# robotek2.net
KiCad netlist of a schematic drawn in EAGLE
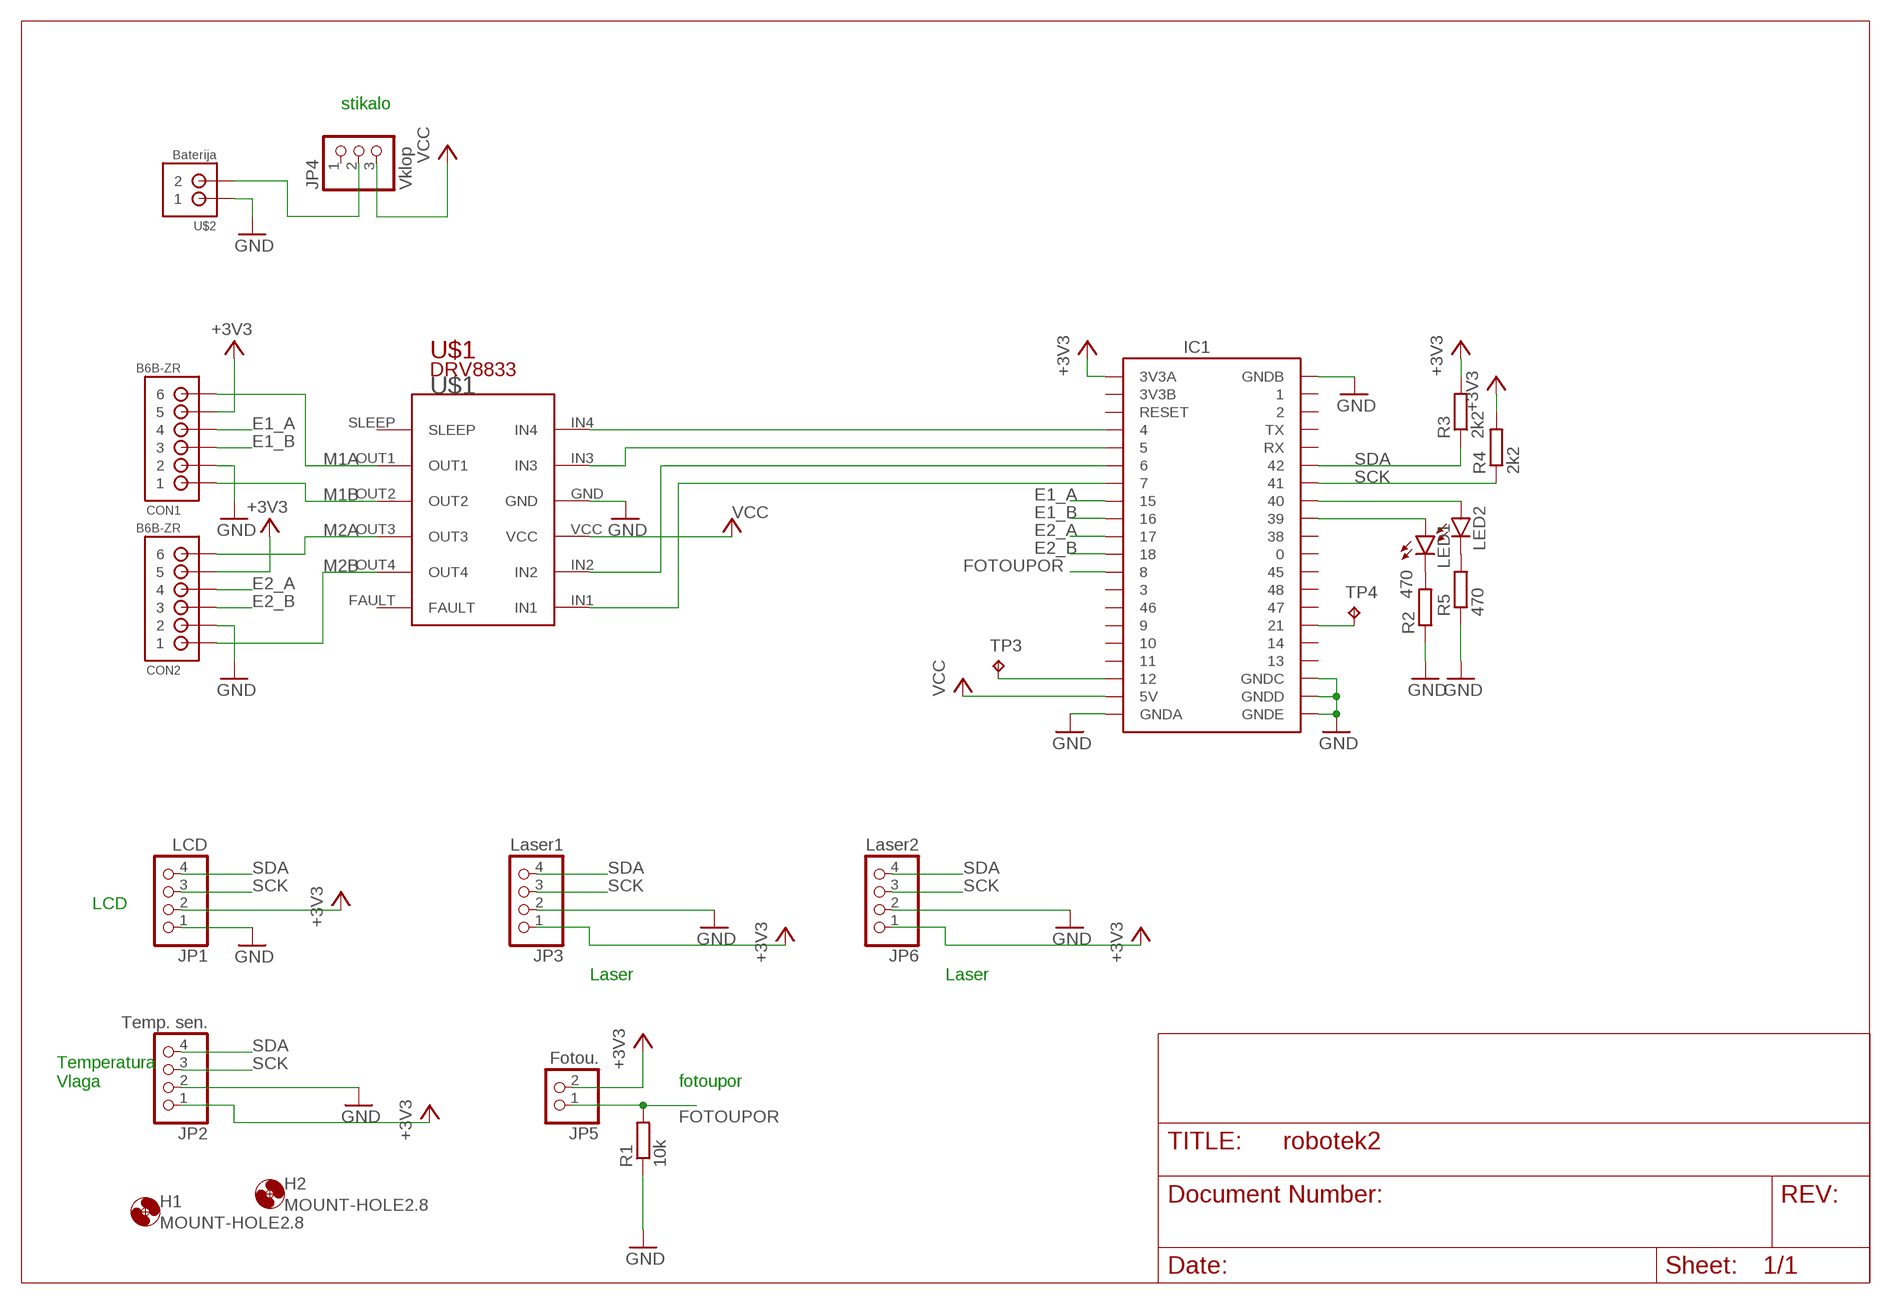
[diagram p0: schematic, sheet 1]

(export (version "E")
  (design (tool "Eeschema 10.0.6"))
  (components
    (comp (ref "CON1")
      (value "B6B-ZR")
      (footprint "eagle-import:B6B-ZR")
      (libsource (lib "eagle-import") (part "B6B-ZR"))
    )
    (comp (ref "CON2")
      (value "B6B-ZR")
      (footprint "eagle-import:B6B-ZR")
      (libsource (lib "eagle-import") (part "B6B-ZR"))
    )
    (comp (ref "H1")
      (value "MOUNT-HOLE2.8")
      (footprint "eagle-import:2,8")
      (libsource (lib "eagle-import") (part "MOUNT-HOLE2.8"))
    )
    (comp (ref "H2")
      (value "MOUNT-HOLE2.8")
      (footprint "eagle-import:2,8")
      (libsource (lib "eagle-import") (part "MOUNT-HOLE2.8"))
    )
    (comp (ref "IC1")
      (value "ESP32_S3")
      (footprint "eagle-import:SSFD_LOLIN32_WEMOS_CHINA_W_BATT")
      (libsource (lib "eagle-import") (part "ESP32_S3"))
    )
    (comp (ref "JP1")
      (value "LCD")
      (footprint "eagle-import:1X04")
      (libsource (lib "eagle-import") (part "PINHD-1X4"))
    )
    (comp (ref "JP2")
      (value "Temp. sen.")
      (footprint "eagle-import:1X04")
      (libsource (lib "eagle-import") (part "PINHD-1X4"))
    )
    (comp (ref "JP3")
      (value "Laser1")
      (footprint "eagle-import:1X04")
      (libsource (lib "eagle-import") (part "PINHD-1X4"))
    )
    (comp (ref "JP4")
      (value "Vklop")
      (footprint "eagle-import:1X03")
      (libsource (lib "eagle-import") (part "PINHD-1X3"))
    )
    (comp (ref "JP5")
      (value "Fotou.")
      (footprint "eagle-import:1X02")
      (libsource (lib "eagle-import") (part "PINHD-1X2"))
    )
    (comp (ref "JP6")
      (value "Laser2")
      (footprint "eagle-import:1X04")
      (libsource (lib "eagle-import") (part "PINHD-1X4"))
    )
    (comp (ref "LED1")
      (value "LEDSML0805")
      (footprint "eagle-import:SML0805")
      (libsource (lib "eagle-import") (part "LEDSML0805"))
    )
    (comp (ref "LED2")
      (value "LEDSML0805")
      (footprint "eagle-import:SML0805")
      (libsource (lib "eagle-import") (part "LEDSML0805"))
    )
    (comp (ref "R1")
      (value "10k")
      (footprint "eagle-import:R1210")
      (libsource (lib "eagle-import") (part "R-EU_R1210"))
    )
    (comp (ref "R2")
      (value "470")
      (footprint "eagle-import:R1210")
      (libsource (lib "eagle-import") (part "R-EU_R1210"))
    )
    (comp (ref "R3")
      (value "2k2")
      (footprint "eagle-import:R0805")
      (libsource (lib "eagle-import") (part "R-EU_R0805"))
    )
    (comp (ref "R4")
      (value "2k2")
      (footprint "eagle-import:R0805")
      (libsource (lib "eagle-import") (part "R-EU_R0805"))
    )
    (comp (ref "R5")
      (value "470")
      (footprint "eagle-import:R1210")
      (libsource (lib "eagle-import") (part "R-EU_R1210"))
    )
    (comp (ref "TP3")
      (value "TPTP20R")
      (footprint "eagle-import:TP20R")
      (libsource (lib "eagle-import") (part "TPTP20R"))
    )
    (comp (ref "TP4")
      (value "TPTP20R")
      (footprint "eagle-import:TP20R")
      (libsource (lib "eagle-import") (part "TPTP20R"))
    )
    (comp (ref "U$1")
      (value "POLOLU-DRV8833")
      (footprint "eagle-import:POLOLU-DRV8833")
      (libsource (lib "eagle-import") (part "POLOLU-DRV8833"))
    )
    (comp (ref "U$2")
      (value "Baterija")
      (footprint "eagle-import:JST_B2B-PH_HEADER")
      (libsource (lib "eagle-import") (part "JST-PH_2-PIN_HEADER"))
    )
  )
  (nets
    (net (code "1") (name "+3V3") (class "Default")
      (node (ref "CON1") (pin "5") (pinfunction "5_5") (pintype "bidirectional"))
      (node (ref "CON2") (pin "5") (pinfunction "5_5") (pintype "bidirectional"))
      (node (ref "IC1") (pin "3V3A") (pinfunction "3V3A_3V3A") (pintype "bidirectional"))
      (node (ref "JP1") (pin "2") (pinfunction "2_2") (pintype "passive"))
      (node (ref "JP2") (pin "1") (pinfunction "1_1") (pintype "passive"))
      (node (ref "JP3") (pin "1") (pinfunction "1_1") (pintype "passive"))
      (node (ref "JP5") (pin "2") (pinfunction "2_2") (pintype "passive"))
      (node (ref "JP6") (pin "1") (pinfunction "1_1") (pintype "passive"))
      (node (ref "R3") (pin "2") (pinfunction "2_2") (pintype "passive"))
      (node (ref "R4") (pin "2") (pinfunction "2_2") (pintype "passive"))
    )
    (net (code "2") (name "/E1_A") (class "Default")
      (node (ref "CON1") (pin "4") (pinfunction "4_4") (pintype "bidirectional"))
      (node (ref "IC1") (pin "15") (pinfunction "15_15") (pintype "bidirectional"))
    )
    (net (code "3") (name "/E1_B") (class "Default")
      (node (ref "CON1") (pin "3") (pinfunction "3_3") (pintype "bidirectional"))
      (node (ref "IC1") (pin "16") (pinfunction "16_16") (pintype "bidirectional"))
    )
    (net (code "4") (name "/E2_A") (class "Default")
      (node (ref "CON2") (pin "4") (pinfunction "4_4") (pintype "bidirectional"))
      (node (ref "IC1") (pin "17") (pinfunction "17_17") (pintype "bidirectional"))
    )
    (net (code "5") (name "/E2_B") (class "Default")
      (node (ref "CON2") (pin "3") (pinfunction "3_3") (pintype "bidirectional"))
      (node (ref "IC1") (pin "18") (pinfunction "18_18") (pintype "bidirectional"))
    )
    (net (code "6") (name "/FOTOUPOR") (class "Default")
      (node (ref "IC1") (pin "8") (pinfunction "8_8") (pintype "bidirectional"))
      (node (ref "JP5") (pin "1") (pinfunction "1_1") (pintype "passive"))
      (node (ref "R1") (pin "2") (pinfunction "2_2") (pintype "passive"))
    )
    (net (code "7") (name "/M1A") (class "Default")
      (node (ref "CON1") (pin "6") (pinfunction "6_6") (pintype "bidirectional"))
      (node (ref "U$1") (pin "OUT1") (pinfunction "OUT1_OUT1") (pintype "bidirectional"))
    )
    (net (code "8") (name "/M1B") (class "Default")
      (node (ref "CON1") (pin "1") (pinfunction "1_1") (pintype "bidirectional"))
      (node (ref "U$1") (pin "OUT2") (pinfunction "OUT2_OUT2") (pintype "bidirectional"))
    )
    (net (code "9") (name "/M2A") (class "Default")
      (node (ref "CON2") (pin "6") (pinfunction "6_6") (pintype "bidirectional"))
      (node (ref "U$1") (pin "OUT3") (pinfunction "OUT3_OUT3") (pintype "bidirectional"))
    )
    (net (code "10") (name "/M2B") (class "Default")
      (node (ref "CON2") (pin "1") (pinfunction "1_1") (pintype "bidirectional"))
      (node (ref "U$1") (pin "OUT4") (pinfunction "OUT4_OUT4") (pintype "bidirectional"))
    )
    (net (code "11") (name "/SCK") (class "Default")
      (node (ref "IC1") (pin "41") (pinfunction "41_41") (pintype "bidirectional"))
      (node (ref "JP1") (pin "3") (pinfunction "3_3") (pintype "passive"))
      (node (ref "JP2") (pin "3") (pinfunction "3_3") (pintype "passive"))
      (node (ref "JP3") (pin "3") (pinfunction "3_3") (pintype "passive"))
      (node (ref "JP6") (pin "3") (pinfunction "3_3") (pintype "passive"))
      (node (ref "R4") (pin "1") (pinfunction "1_1") (pintype "passive"))
    )
    (net (code "12") (name "/SDA") (class "Default")
      (node (ref "IC1") (pin "42") (pinfunction "42_42") (pintype "bidirectional"))
      (node (ref "JP1") (pin "4") (pinfunction "4_4") (pintype "passive"))
      (node (ref "JP2") (pin "4") (pinfunction "4_4") (pintype "passive"))
      (node (ref "JP3") (pin "4") (pinfunction "4_4") (pintype "passive"))
      (node (ref "JP6") (pin "4") (pinfunction "4_4") (pintype "passive"))
      (node (ref "R3") (pin "1") (pinfunction "1_1") (pintype "passive"))
    )
    (net (code "13") (name "GND") (class "Default")
      (node (ref "CON1") (pin "2") (pinfunction "2_2") (pintype "bidirectional"))
      (node (ref "CON2") (pin "2") (pinfunction "2_2") (pintype "bidirectional"))
      (node (ref "IC1") (pin "GNDA4") (pinfunction "GNDA_GNDA4") (pintype "bidirectional"))
      (node (ref "IC1") (pin "GNDB") (pinfunction "GNDB_GNDB") (pintype "bidirectional"))
      (node (ref "IC1") (pin "GNDC1") (pinfunction "GNDC_GNDC1") (pintype "bidirectional"))
      (node (ref "IC1") (pin "GNDD1") (pinfunction "GNDD_GNDD1") (pintype "bidirectional"))
      (node (ref "IC1") (pin "GNDE") (pinfunction "GNDE_GNDE") (pintype "bidirectional"))
      (node (ref "JP1") (pin "1") (pinfunction "1_1") (pintype "passive"))
      (node (ref "JP2") (pin "2") (pinfunction "2_2") (pintype "passive"))
      (node (ref "JP3") (pin "2") (pinfunction "2_2") (pintype "passive"))
      (node (ref "JP6") (pin "2") (pinfunction "2_2") (pintype "passive"))
      (node (ref "R1") (pin "1") (pinfunction "1_1") (pintype "passive"))
      (node (ref "R2") (pin "1") (pinfunction "1_1") (pintype "passive"))
      (node (ref "R5") (pin "1") (pinfunction "1_1") (pintype "passive"))
      (node (ref "U$1") (pin "GND") (pinfunction "GND_GND") (pintype "power_in"))
      (node (ref "U$2") (pin "P1") (pinfunction "1_P1") (pintype "bidirectional"))
    )
    (net (code "14") (name "Net-(IC1-Pad4)") (class "Default")
      (node (ref "IC1") (pin "4") (pinfunction "4_4") (pintype "bidirectional"))
      (node (ref "U$1") (pin "IN4") (pinfunction "IN4_IN4") (pintype "bidirectional"))
    )
    (net (code "15") (name "Net-(IC1-Pad5)") (class "Default")
      (node (ref "IC1") (pin "5") (pinfunction "5_5") (pintype "bidirectional"))
      (node (ref "U$1") (pin "IN3") (pinfunction "IN3_IN3") (pintype "bidirectional"))
    )
    (net (code "16") (name "Net-(IC1-Pad6)") (class "Default")
      (node (ref "IC1") (pin "6") (pinfunction "6_6") (pintype "bidirectional"))
      (node (ref "U$1") (pin "IN2") (pinfunction "IN2_IN2") (pintype "bidirectional"))
    )
    (net (code "17") (name "Net-(IC1-Pad7)") (class "Default")
      (node (ref "IC1") (pin "7") (pinfunction "7_7") (pintype "bidirectional"))
      (node (ref "U$1") (pin "IN1") (pinfunction "IN1_IN1") (pintype "bidirectional"))
    )
    (net (code "18") (name "Net-(IC1-Pad12)") (class "Default")
      (node (ref "IC1") (pin "12") (pinfunction "12_12") (pintype "bidirectional"))
      (node (ref "TP3") (pin "TP") (pinfunction "TP_TP") (pintype "input"))
    )
    (net (code "19") (name "Net-(IC1-Pad21)") (class "Default")
      (node (ref "IC1") (pin "21") (pinfunction "21_21") (pintype "bidirectional"))
      (node (ref "TP4") (pin "TP") (pinfunction "TP_TP") (pintype "input"))
    )
    (net (code "20") (name "Net-(IC1-Pad39)") (class "Default")
      (node (ref "IC1") (pin "39") (pinfunction "39_39") (pintype "bidirectional"))
      (node (ref "LED1") (pin "A") (pinfunction "A_A") (pintype "passive"))
    )
    (net (code "21") (name "Net-(IC1-Pad40)") (class "Default")
      (node (ref "IC1") (pin "40") (pinfunction "40_40") (pintype "bidirectional"))
      (node (ref "LED2") (pin "A") (pinfunction "A_A") (pintype "passive"))
    )
    (net (code "22") (name "Net-(LED1-PadC)") (class "Default")
      (node (ref "LED1") (pin "C") (pinfunction "C_C") (pintype "passive"))
      (node (ref "R2") (pin "2") (pinfunction "2_2") (pintype "passive"))
    )
    (net (code "23") (name "Net-(LED2-PadC)") (class "Default")
      (node (ref "LED2") (pin "C") (pinfunction "C_C") (pintype "passive"))
      (node (ref "R5") (pin "2") (pinfunction "2_2") (pintype "passive"))
    )
    (net (code "24") (name "Net-(U$2-2)") (class "Default")
      (node (ref "JP4") (pin "2") (pinfunction "2_2") (pintype "passive"))
      (node (ref "U$2") (pin "P2") (pinfunction "2_P2") (pintype "bidirectional"))
    )
    (net (code "25") (name "VCC") (class "Default")
      (node (ref "IC1") (pin "5V") (pinfunction "5V_5V") (pintype "bidirectional"))
      (node (ref "JP4") (pin "3") (pinfunction "3_3") (pintype "passive"))
      (node (ref "U$1") (pin "VCC") (pinfunction "VCC_VCC") (pintype "power_in"))
    )
    (net (code "26") (name "unconnected-(IC1-3V3B-Pad3V3D1)") (class "Default")
      (node (ref "IC1") (pin "3V3D1") (pinfunction "3V3B_3V3D1") (pintype "bidirectional"))
    )
    (net (code "27") (name "unconnected-(IC1-Pad0)") (class "Default")
      (node (ref "IC1") (pin "0") (pinfunction "0_0") (pintype "bidirectional"))
    )
    (net (code "28") (name "unconnected-(IC1-Pad1)") (class "Default")
      (node (ref "IC1") (pin "1") (pinfunction "1_1") (pintype "bidirectional"))
    )
    (net (code "29") (name "unconnected-(IC1-Pad2)") (class "Default")
      (node (ref "IC1") (pin "2") (pinfunction "2_2") (pintype "bidirectional"))
    )
    (net (code "30") (name "unconnected-(IC1-Pad3)") (class "Default")
      (node (ref "IC1") (pin "3") (pinfunction "3_3") (pintype "bidirectional"))
    )
    (net (code "31") (name "unconnected-(IC1-Pad9)") (class "Default")
      (node (ref "IC1") (pin "9") (pinfunction "9_9") (pintype "bidirectional"))
    )
    (net (code "32") (name "unconnected-(IC1-Pad10)") (class "Default")
      (node (ref "IC1") (pin "10") (pinfunction "10_10") (pintype "bidirectional"))
    )
    (net (code "33") (name "unconnected-(IC1-Pad11)") (class "Default")
      (node (ref "IC1") (pin "11") (pinfunction "11_11") (pintype "bidirectional"))
    )
    (net (code "34") (name "unconnected-(IC1-Pad13)") (class "Default")
      (node (ref "IC1") (pin "13") (pinfunction "13_13") (pintype "bidirectional"))
    )
    (net (code "35") (name "unconnected-(IC1-Pad14)") (class "Default")
      (node (ref "IC1") (pin "14") (pinfunction "14_14") (pintype "bidirectional"))
    )
    (net (code "36") (name "unconnected-(IC1-Pad38)") (class "Default")
      (node (ref "IC1") (pin "38") (pinfunction "38_38") (pintype "bidirectional"))
    )
    (net (code "37") (name "unconnected-(IC1-Pad45)") (class "Default")
      (node (ref "IC1") (pin "45") (pinfunction "45_45") (pintype "bidirectional"))
    )
    (net (code "38") (name "unconnected-(IC1-Pad46)") (class "Default")
      (node (ref "IC1") (pin "46") (pinfunction "46_46") (pintype "bidirectional"))
    )
    (net (code "39") (name "unconnected-(IC1-Pad47)") (class "Default")
      (node (ref "IC1") (pin "47") (pinfunction "47_47") (pintype "bidirectional"))
    )
    (net (code "40") (name "unconnected-(IC1-Pad48)") (class "Default")
      (node (ref "IC1") (pin "48") (pinfunction "48_48") (pintype "bidirectional"))
    )
    (net (code "41") (name "unconnected-(IC1-PadRESET)") (class "Default")
      (node (ref "IC1") (pin "RESET") (pinfunction "RESET_RESET") (pintype "bidirectional"))
    )
    (net (code "42") (name "unconnected-(IC1-PadRX)") (class "Default")
      (node (ref "IC1") (pin "RX") (pinfunction "RX_RX") (pintype "bidirectional"))
    )
    (net (code "43") (name "unconnected-(IC1-PadTX)") (class "Default")
      (node (ref "IC1") (pin "TX") (pinfunction "TX_TX") (pintype "bidirectional"))
    )
    (net (code "44") (name "unconnected-(JP4-Pad1)") (class "Default")
      (node (ref "JP4") (pin "1") (pinfunction "1_1") (pintype "passive"))
    )
    (net (code "45") (name "unconnected-(U$1-PadFAULT)") (class "Default")
      (node (ref "U$1") (pin "FAULT") (pinfunction "FAULT_FAULT") (pintype "bidirectional"))
    )
    (net (code "46") (name "unconnected-(U$1-PadSLEEP)") (class "Default")
      (node (ref "U$1") (pin "SLEEP") (pinfunction "SLEEP_SLEEP") (pintype "bidirectional"))
    )
  )
)
